# PCB_Albert.net
KiCad netlist of a schematic drawn in EAGLE
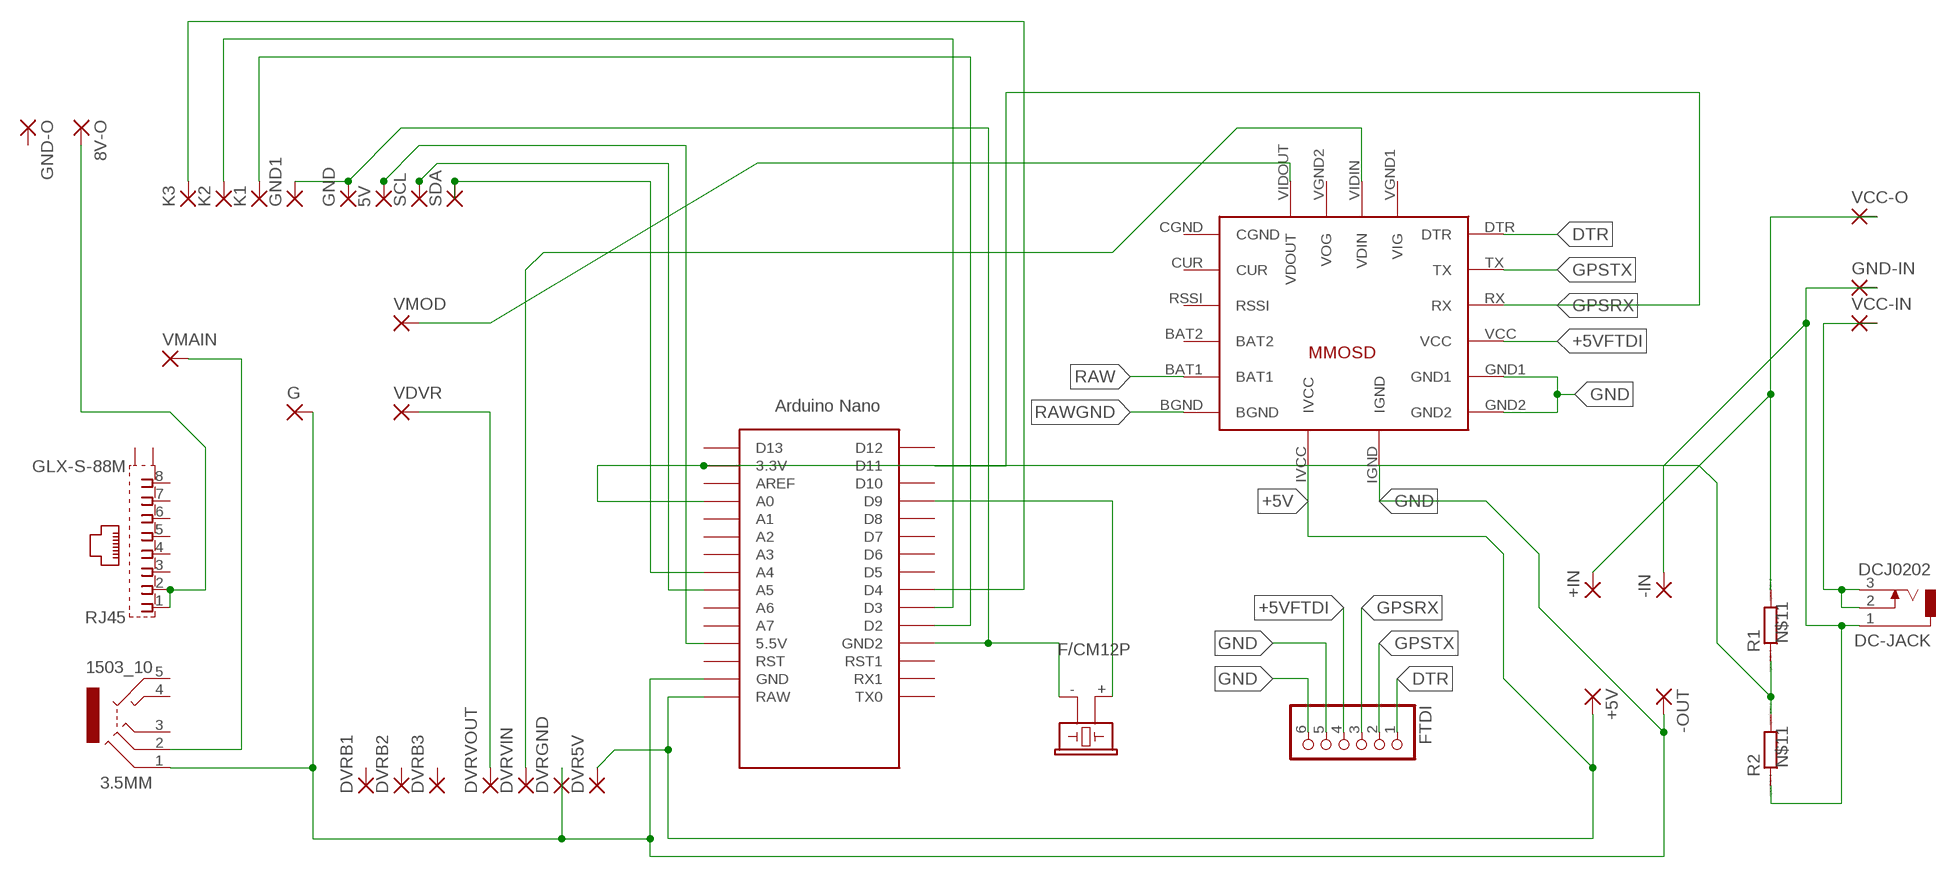
[diagram p0: schematic, sheet 1]

(export (version "E")
  (design (tool "Eeschema 10.0.6"))
  (components
    (comp (ref "+5V")
      (value "SMD2")
      (footprint "eagle-import:SMD1,27-2,54")
      (libsource (lib "eagle-import") (part "SMD2"))
    )
    (comp (ref "+IN")
      (value "SMD2")
      (footprint "eagle-import:SMD1,27-2,54")
      (libsource (lib "eagle-import") (part "SMD2"))
    )
    (comp (ref "-IN")
      (value "SMD2")
      (footprint "eagle-import:SMD1,27-2,54")
      (libsource (lib "eagle-import") (part "SMD2"))
    )
    (comp (ref "-OUT")
      (value "SMD2")
      (footprint "eagle-import:SMD1,27-2,54")
      (libsource (lib "eagle-import") (part "SMD2"))
    )
    (comp (ref "3.5MM")
      (value "1503_10")
      (footprint "eagle-import:1503_10")
      (libsource (lib "eagle-import") (part "1503_10"))
    )
    (comp (ref "5V")
      (value "SMD2")
      (footprint "eagle-import:SMD1,27-2,54")
      (libsource (lib "eagle-import") (part "SMD2"))
    )
    (comp (ref "8V-O")
      (value "2,54/1,1")
      (footprint "eagle-import:2,54_1,1")
      (libsource (lib "eagle-import") (part "2,54/1,1"))
    )
    (comp (ref "ADRUINO-NANO")
      (value "NANO")
      (footprint "eagle-import:NANO")
      (libsource (lib "eagle-import") (part "NANO"))
    )
    (comp (ref "BUZZ")
      (value "F/CM12P")
      (footprint "eagle-import:F_CM12P")
      (fields (field (name "SPICEPREFIX") "X"))
      (libsource (lib "eagle-import") (part "F/CM12P"))
    )
    (comp (ref "DC-JACK")
      (value "DCJ0202")
      (footprint "eagle-import:DCJ0202")
      (libsource (lib "eagle-import") (part "DCJ0202"))
    )
    (comp (ref "DVR5V")
      (value "SMD2")
      (footprint "eagle-import:SMD1,27-2,54")
      (libsource (lib "eagle-import") (part "SMD2"))
    )
    (comp (ref "DVRB1")
      (value "SMD2")
      (footprint "eagle-import:SMD1,27-2,54")
      (libsource (lib "eagle-import") (part "SMD2"))
    )
    (comp (ref "DVRB2")
      (value "SMD2")
      (footprint "eagle-import:SMD1,27-2,54")
      (libsource (lib "eagle-import") (part "SMD2"))
    )
    (comp (ref "DVRB3")
      (value "SMD2")
      (footprint "eagle-import:SMD1,27-2,54")
      (libsource (lib "eagle-import") (part "SMD2"))
    )
    (comp (ref "DVRGND")
      (value "SMD2")
      (footprint "eagle-import:SMD1,27-2,54")
      (libsource (lib "eagle-import") (part "SMD2"))
    )
    (comp (ref "DVRVIN")
      (value "SMD2")
      (footprint "eagle-import:SMD1,27-2,54")
      (libsource (lib "eagle-import") (part "SMD2"))
    )
    (comp (ref "DVRVOUT")
      (value "SMD2")
      (footprint "eagle-import:SMD1,27-2,54")
      (libsource (lib "eagle-import") (part "SMD2"))
    )
    (comp (ref "FTDI")
      (value "PINHD-1X6")
      (footprint "eagle-import:1X06")
      (libsource (lib "eagle-import") (part "PINHD-1X6"))
    )
    (comp (ref "G")
      (value "SMD2")
      (footprint "eagle-import:SMD1,27-2,54")
      (libsource (lib "eagle-import") (part "SMD2"))
    )
    (comp (ref "GND")
      (value "SMD2")
      (footprint "eagle-import:SMD1,27-2,54")
      (libsource (lib "eagle-import") (part "SMD2"))
    )
    (comp (ref "GND-IN")
      (value "2,54/1,1")
      (footprint "eagle-import:2,54_1,1")
      (libsource (lib "eagle-import") (part "2,54/1,1"))
    )
    (comp (ref "GND-O")
      (value "2,54/1,1")
      (footprint "eagle-import:2,54_1,1")
      (libsource (lib "eagle-import") (part "2,54/1,1"))
    )
    (comp (ref "GND1")
      (value "SMD2")
      (footprint "eagle-import:SMD1,27-2,54")
      (libsource (lib "eagle-import") (part "SMD2"))
    )
    (comp (ref "K1")
      (value "SMD2")
      (footprint "eagle-import:SMD1,27-2,54")
      (libsource (lib "eagle-import") (part "SMD2"))
    )
    (comp (ref "K2")
      (value "SMD2")
      (footprint "eagle-import:SMD1,27-2,54")
      (libsource (lib "eagle-import") (part "SMD2"))
    )
    (comp (ref "K3")
      (value "SMD2")
      (footprint "eagle-import:SMD1,27-2,54")
      (libsource (lib "eagle-import") (part "SMD2"))
    )
    (comp (ref "MINIMOSD")
      (value "MICROMINIMOSDPWR")
      (footprint "eagle-import:MMOSDNVDVID")
      (libsource (lib "eagle-import") (part "MICROMINIMOSDPWR"))
    )
    (comp (ref "R1")
      (value "R0207/10")
      (footprint "eagle-import:0207_10")
      (libsource (lib "eagle-import") (part "R0207/10"))
    )
    (comp (ref "R2")
      (value "R0207/10")
      (footprint "eagle-import:0207_10")
      (libsource (lib "eagle-import") (part "R0207/10"))
    )
    (comp (ref "RJ45")
      (value "GLX-S-88M")
      (footprint "eagle-import:GLX-S-88M")
      (libsource (lib "eagle-import") (part "GLX-S-88M"))
    )
    (comp (ref "SCL")
      (value "SMD2")
      (footprint "eagle-import:SMD1,27-2,54")
      (libsource (lib "eagle-import") (part "SMD2"))
    )
    (comp (ref "SDA")
      (value "SMD2")
      (footprint "eagle-import:SMD1,27-2,54")
      (libsource (lib "eagle-import") (part "SMD2"))
    )
    (comp (ref "VCC-IN")
      (value "2,54/1,1")
      (footprint "eagle-import:2,54_1,1")
      (libsource (lib "eagle-import") (part "2,54/1,1"))
    )
    (comp (ref "VCC-O")
      (value "2,54/1,1")
      (footprint "eagle-import:2,54_1,1")
      (libsource (lib "eagle-import") (part "2,54/1,1"))
    )
    (comp (ref "VDVR")
      (value "SMD2")
      (footprint "eagle-import:SMD1,27-2,54")
      (libsource (lib "eagle-import") (part "SMD2"))
    )
    (comp (ref "VMAIN")
      (value "SMD2")
      (footprint "eagle-import:SMD1,27-2,54")
      (libsource (lib "eagle-import") (part "SMD2"))
    )
    (comp (ref "VMOD")
      (value "SMD2")
      (footprint "eagle-import:SMD1,27-2,54")
      (libsource (lib "eagle-import") (part "SMD2"))
    )
  )
  (nets
    (net (code "1") (name "+5V") (class "Default")
      (node (ref "+5V") (pin "1") (pinfunction "P_1") (pintype "passive"))
      (node (ref "ADRUINO-NANO") (pin "RAW") (pinfunction "RAW_RAW") (pintype "bidirectional"))
      (node (ref "DVR5V") (pin "1") (pinfunction "P_1") (pintype "passive"))
      (node (ref "MINIMOSD") (pin "IVCC") (pinfunction "IVCC_IVCC") (pintype "power_in"))
    )
    (net (code "2") (name "+5VFTDI") (class "Default")
      (node (ref "FTDI") (pin "4") (pinfunction "4_4") (pintype "passive"))
      (node (ref "MINIMOSD") (pin "VCC") (pinfunction "VCC_VCC") (pintype "power_in"))
    )
    (net (code "3") (name "/BAT2") (class "Default")
      (node (ref "MINIMOSD") (pin "BAT2") (pinfunction "BAT2_BAT2") (pintype "power_in"))
    )
    (net (code "4") (name "/CGND") (class "Default")
      (node (ref "MINIMOSD") (pin "CGND") (pinfunction "CGND_CGND") (pintype "power_in"))
    )
    (net (code "5") (name "/N$11") (class "Default")
      (node (ref "-IN") (pin "1") (pinfunction "P_1") (pintype "passive"))
      (node (ref "DC-JACK") (pin "1") (pinfunction "1_1") (pintype "passive"))
      (node (ref "GND-IN") (pin "1") (pinfunction "P_1") (pintype "passive"))
      (node (ref "R2") (pin "1") (pinfunction "1_1") (pintype "passive"))
    )
    (net (code "6") (name "DTR") (class "Default")
      (node (ref "FTDI") (pin "1") (pinfunction "1_1") (pintype "passive"))
      (node (ref "MINIMOSD") (pin "DTR") (pinfunction "DTR_DTR") (pintype "bidirectional"))
    )
    (net (code "7") (name "GND") (class "Default")
      (node (ref "-OUT") (pin "1") (pinfunction "P_1") (pintype "passive"))
      (node (ref "3.5MM") (pin "1") (pinfunction "1_1") (pintype "passive"))
      (node (ref "ADRUINO-NANO") (pin "GND") (pinfunction "GND_GND") (pintype "bidirectional"))
      (node (ref "DVRGND") (pin "1") (pinfunction "P_1") (pintype "passive"))
      (node (ref "FTDI") (pin "5") (pinfunction "5_5") (pintype "passive"))
      (node (ref "FTDI") (pin "6") (pinfunction "6_6") (pintype "passive"))
      (node (ref "G") (pin "1") (pinfunction "P_1") (pintype "passive"))
      (node (ref "MINIMOSD") (pin "GND1") (pinfunction "GND1_GND1") (pintype "power_in"))
      (node (ref "MINIMOSD") (pin "GND2") (pinfunction "GND2_GND2") (pintype "power_in"))
      (node (ref "MINIMOSD") (pin "IGND") (pinfunction "IGND_IGND") (pintype "power_in"))
    )
    (net (code "8") (name "GPSRX") (class "Default")
      (node (ref "ADRUINO-NANO") (pin "D11") (pinfunction "D11_D11") (pintype "bidirectional"))
      (node (ref "FTDI") (pin "3") (pinfunction "3_3") (pintype "passive"))
      (node (ref "MINIMOSD") (pin "RX") (pinfunction "RX_RX") (pintype "input"))
    )
    (net (code "9") (name "GPSTX") (class "Default")
      (node (ref "FTDI") (pin "2") (pinfunction "2_2") (pintype "passive"))
      (node (ref "MINIMOSD") (pin "TX") (pinfunction "TX_TX") (pintype "output"))
    )
    (net (code "10") (name "Net-(+IN-P)") (class "Default")
      (node (ref "+IN") (pin "1") (pinfunction "P_1") (pintype "passive"))
      (node (ref "R1") (pin "2") (pinfunction "2_2") (pintype "passive"))
      (node (ref "VCC-O") (pin "1") (pinfunction "P_1") (pintype "passive"))
    )
    (net (code "11") (name "Net-(5V-P)") (class "Default")
      (node (ref "5V") (pin "1") (pinfunction "P_1") (pintype "passive"))
      (node (ref "ADRUINO-NANO") (pin "5V") (pinfunction "5.5V_5V") (pintype "bidirectional"))
    )
    (net (code "12") (name "Net-(8V-O-P)") (class "Default")
      (node (ref "8V-O") (pin "1") (pinfunction "P_1") (pintype "passive"))
      (node (ref "RJ45") (pin "1") (pinfunction "1_1") (pintype "passive"))
      (node (ref "RJ45") (pin "2") (pinfunction "2_2") (pintype "passive"))
    )
    (net (code "13") (name "Net-(ADRUINO-NANO-GND2)") (class "Default")
      (node (ref "ADRUINO-NANO") (pin "GND1") (pinfunction "GND2_GND1") (pintype "bidirectional"))
      (node (ref "BUZZ") (pin "-") (pinfunction "2_-") (pintype "passive"))
      (node (ref "GND") (pin "1") (pinfunction "P_1") (pintype "passive"))
      (node (ref "GND1") (pin "1") (pinfunction "P_1") (pintype "passive"))
    )
    (net (code "14") (name "Net-(ADRUINO-NANO-Pad3.3V)") (class "Default")
      (node (ref "ADRUINO-NANO") (pin "3.3V") (pinfunction "3.3V_3.3V") (pintype "bidirectional"))
      (node (ref "ADRUINO-NANO") (pin "A0") (pinfunction "A0_A0") (pintype "bidirectional"))
      (node (ref "R1") (pin "1") (pinfunction "1_1") (pintype "passive"))
      (node (ref "R2") (pin "2") (pinfunction "2_2") (pintype "passive"))
    )
    (net (code "15") (name "Net-(BUZZ-1)") (class "Default")
      (node (ref "ADRUINO-NANO") (pin "D9") (pinfunction "D9_D9") (pintype "bidirectional"))
      (node (ref "BUZZ") (pin "+") (pinfunction "1_+") (pintype "passive"))
    )
    (net (code "16") (name "Net-(DVRVIN-P)") (class "Default")
      (node (ref "DVRVIN") (pin "1") (pinfunction "P_1") (pintype "passive"))
      (node (ref "MINIMOSD") (pin "VIDIN") (pinfunction "VDIN_VIDIN") (pintype "input"))
    )
    (net (code "17") (name "Net-(DVRVOUT-P)") (class "Default")
      (node (ref "DVRVOUT") (pin "1") (pinfunction "P_1") (pintype "passive"))
      (node (ref "VDVR") (pin "1") (pinfunction "P_1") (pintype "passive"))
    )
    (net (code "18") (name "Net-(K1-P)") (class "Default")
      (node (ref "ADRUINO-NANO") (pin "D2") (pinfunction "D2_D2") (pintype "bidirectional"))
      (node (ref "K1") (pin "1") (pinfunction "P_1") (pintype "passive"))
    )
    (net (code "19") (name "Net-(K2-P)") (class "Default")
      (node (ref "ADRUINO-NANO") (pin "D3") (pinfunction "D3_D3") (pintype "bidirectional"))
      (node (ref "K2") (pin "1") (pinfunction "P_1") (pintype "passive"))
    )
    (net (code "20") (name "Net-(K3-P)") (class "Default")
      (node (ref "ADRUINO-NANO") (pin "D4") (pinfunction "D4_D4") (pintype "bidirectional"))
      (node (ref "K3") (pin "1") (pinfunction "P_1") (pintype "passive"))
    )
    (net (code "21") (name "Net-(MINIMOSD-VDOUT)") (class "Default")
      (node (ref "MINIMOSD") (pin "VIDOUT") (pinfunction "VDOUT_VIDOUT") (pintype "output"))
      (node (ref "VMOD") (pin "1") (pinfunction "P_1") (pintype "passive"))
    )
    (net (code "22") (name "Net-(SCL-P)") (class "Default")
      (node (ref "ADRUINO-NANO") (pin "A5") (pinfunction "A5_A5") (pintype "bidirectional"))
      (node (ref "SCL") (pin "1") (pinfunction "P_1") (pintype "passive"))
    )
    (net (code "23") (name "Net-(SDA-P)") (class "Default")
      (node (ref "ADRUINO-NANO") (pin "A4") (pinfunction "A4_A4") (pintype "bidirectional"))
      (node (ref "SDA") (pin "1") (pinfunction "P_1") (pintype "passive"))
    )
    (net (code "24") (name "Net-(VCC-IN-P)") (class "Default")
      (node (ref "DC-JACK") (pin "2") (pinfunction "2_2") (pintype "passive"))
      (node (ref "DC-JACK") (pin "3") (pinfunction "3_3") (pintype "passive"))
      (node (ref "VCC-IN") (pin "1") (pinfunction "P_1") (pintype "passive"))
    )
    (net (code "25") (name "Net-(VMAIN-P)") (class "Default")
      (node (ref "3.5MM") (pin "2") (pinfunction "2_2") (pintype "passive"))
      (node (ref "VMAIN") (pin "1") (pinfunction "P_1") (pintype "passive"))
    )
    (net (code "26") (name "RAW") (class "Default")
      (node (ref "MINIMOSD") (pin "BAT1") (pinfunction "BAT1_BAT1") (pintype "power_in"))
    )
    (net (code "27") (name "RAWGND") (class "Default")
      (node (ref "MINIMOSD") (pin "BGND") (pinfunction "BGND_BGND") (pintype "power_in"))
    )
    (net (code "28") (name "unconnected-(3.5MM-Pad3)") (class "Default")
      (node (ref "3.5MM") (pin "3") (pinfunction "3_3") (pintype "passive"))
    )
    (net (code "29") (name "unconnected-(3.5MM-Pad4)") (class "Default")
      (node (ref "3.5MM") (pin "4") (pinfunction "4_4") (pintype "passive"))
    )
    (net (code "30") (name "unconnected-(3.5MM-Pad5)") (class "Default")
      (node (ref "3.5MM") (pin "5") (pinfunction "5_5") (pintype "passive"))
    )
    (net (code "31") (name "unconnected-(ADRUINO-NANO-PadA1)") (class "Default")
      (node (ref "ADRUINO-NANO") (pin "A1") (pinfunction "A1_A1") (pintype "bidirectional"))
    )
    (net (code "32") (name "unconnected-(ADRUINO-NANO-PadA2)") (class "Default")
      (node (ref "ADRUINO-NANO") (pin "A2") (pinfunction "A2_A2") (pintype "bidirectional"))
    )
    (net (code "33") (name "unconnected-(ADRUINO-NANO-PadA3)") (class "Default")
      (node (ref "ADRUINO-NANO") (pin "A3") (pinfunction "A3_A3") (pintype "bidirectional"))
    )
    (net (code "34") (name "unconnected-(ADRUINO-NANO-PadA6)") (class "Default")
      (node (ref "ADRUINO-NANO") (pin "A6") (pinfunction "A6_A6") (pintype "bidirectional"))
    )
    (net (code "35") (name "unconnected-(ADRUINO-NANO-PadA7)") (class "Default")
      (node (ref "ADRUINO-NANO") (pin "A7") (pinfunction "A7_A7") (pintype "bidirectional"))
    )
    (net (code "36") (name "unconnected-(ADRUINO-NANO-PadAREF)") (class "Default")
      (node (ref "ADRUINO-NANO") (pin "AREF") (pinfunction "AREF_AREF") (pintype "bidirectional"))
    )
    (net (code "37") (name "unconnected-(ADRUINO-NANO-PadD5)") (class "Default")
      (node (ref "ADRUINO-NANO") (pin "D5") (pinfunction "D5_D5") (pintype "bidirectional"))
    )
    (net (code "38") (name "unconnected-(ADRUINO-NANO-PadD6)") (class "Default")
      (node (ref "ADRUINO-NANO") (pin "D6") (pinfunction "D6_D6") (pintype "bidirectional"))
    )
    (net (code "39") (name "unconnected-(ADRUINO-NANO-PadD7)") (class "Default")
      (node (ref "ADRUINO-NANO") (pin "D7") (pinfunction "D7_D7") (pintype "bidirectional"))
    )
    (net (code "40") (name "unconnected-(ADRUINO-NANO-PadD8)") (class "Default")
      (node (ref "ADRUINO-NANO") (pin "D8") (pinfunction "D8_D8") (pintype "bidirectional"))
    )
    (net (code "41") (name "unconnected-(ADRUINO-NANO-PadD10)") (class "Default")
      (node (ref "ADRUINO-NANO") (pin "D10") (pinfunction "D10_D10") (pintype "bidirectional"))
    )
    (net (code "42") (name "unconnected-(ADRUINO-NANO-PadD12)") (class "Default")
      (node (ref "ADRUINO-NANO") (pin "D12") (pinfunction "D12_D12") (pintype "bidirectional"))
    )
    (net (code "43") (name "unconnected-(ADRUINO-NANO-PadD13)") (class "Default")
      (node (ref "ADRUINO-NANO") (pin "D13") (pinfunction "D13_D13") (pintype "bidirectional"))
    )
    (net (code "44") (name "unconnected-(ADRUINO-NANO-PadICSP1)") (class "Default")
      (node (ref "ADRUINO-NANO") (pin "ICSP1") (pinfunction "ICSP1_ICSP1") (pintype "bidirectional"))
    )
    (net (code "45") (name "unconnected-(ADRUINO-NANO-PadICSP2)") (class "Default")
      (node (ref "ADRUINO-NANO") (pin "ICSP2") (pinfunction "ICSP2_ICSP2") (pintype "bidirectional"))
    )
    (net (code "46") (name "unconnected-(ADRUINO-NANO-PadICSP3)") (class "Default")
      (node (ref "ADRUINO-NANO") (pin "ICSP3") (pinfunction "ICSP3_ICSP3") (pintype "bidirectional"))
    )
    (net (code "47") (name "unconnected-(ADRUINO-NANO-PadICSP4)") (class "Default")
      (node (ref "ADRUINO-NANO") (pin "ICSP4") (pinfunction "ICSP4_ICSP4") (pintype "bidirectional"))
    )
    (net (code "48") (name "unconnected-(ADRUINO-NANO-PadICSP5)") (class "Default")
      (node (ref "ADRUINO-NANO") (pin "ICSP5") (pinfunction "ICSP5_ICSP5") (pintype "bidirectional"))
    )
    (net (code "49") (name "unconnected-(ADRUINO-NANO-PadICSP6)") (class "Default")
      (node (ref "ADRUINO-NANO") (pin "ICSP6") (pinfunction "ICSP6_ICSP6") (pintype "bidirectional"))
    )
    (net (code "50") (name "unconnected-(ADRUINO-NANO-PadRST)") (class "Default")
      (node (ref "ADRUINO-NANO") (pin "RST") (pinfunction "RST_RST") (pintype "bidirectional"))
    )
    (net (code "51") (name "unconnected-(ADRUINO-NANO-PadRST1)") (class "Default")
      (node (ref "ADRUINO-NANO") (pin "RST1") (pinfunction "RST1_RST1") (pintype "bidirectional"))
    )
    (net (code "52") (name "unconnected-(ADRUINO-NANO-PadRX1)") (class "Default")
      (node (ref "ADRUINO-NANO") (pin "RX1") (pinfunction "RX1_RX1") (pintype "bidirectional"))
    )
    (net (code "53") (name "unconnected-(ADRUINO-NANO-PadTX0)") (class "Default")
      (node (ref "ADRUINO-NANO") (pin "TX0") (pinfunction "TX0_TX0") (pintype "bidirectional"))
    )
    (net (code "54") (name "unconnected-(DVRB1-P-Pad1)") (class "Default")
      (node (ref "DVRB1") (pin "1") (pinfunction "P_1") (pintype "passive"))
    )
    (net (code "55") (name "unconnected-(DVRB2-P-Pad1)") (class "Default")
      (node (ref "DVRB2") (pin "1") (pinfunction "P_1") (pintype "passive"))
    )
    (net (code "56") (name "unconnected-(DVRB3-P-Pad1)") (class "Default")
      (node (ref "DVRB3") (pin "1") (pinfunction "P_1") (pintype "passive"))
    )
    (net (code "57") (name "unconnected-(GND-O-P-Pad1)") (class "Default")
      (node (ref "GND-O") (pin "1") (pinfunction "P_1") (pintype "passive"))
    )
    (net (code "58") (name "unconnected-(MINIMOSD-PadCUR)") (class "Default")
      (node (ref "MINIMOSD") (pin "CUR") (pinfunction "CUR_CUR") (pintype "bidirectional"))
    )
    (net (code "59") (name "unconnected-(MINIMOSD-PadRSSI)") (class "Default")
      (node (ref "MINIMOSD") (pin "RSSI") (pinfunction "RSSI_RSSI") (pintype "bidirectional"))
    )
    (net (code "60") (name "unconnected-(MINIMOSD-VIG-PadVGND1)") (class "Default")
      (node (ref "MINIMOSD") (pin "VGND1") (pinfunction "VIG_VGND1") (pintype "input"))
    )
    (net (code "61") (name "unconnected-(MINIMOSD-VOG-PadVGND2)") (class "Default")
      (node (ref "MINIMOSD") (pin "VGND2") (pinfunction "VOG_VGND2") (pintype "output"))
    )
    (net (code "62") (name "unconnected-(RJ45-Pad3)") (class "Default")
      (node (ref "RJ45") (pin "3") (pinfunction "3_3") (pintype "passive"))
    )
    (net (code "63") (name "unconnected-(RJ45-Pad4)") (class "Default")
      (node (ref "RJ45") (pin "4") (pinfunction "4_4") (pintype "passive"))
    )
    (net (code "64") (name "unconnected-(RJ45-Pad5)") (class "Default")
      (node (ref "RJ45") (pin "5") (pinfunction "5_5") (pintype "passive"))
    )
    (net (code "65") (name "unconnected-(RJ45-Pad6)") (class "Default")
      (node (ref "RJ45") (pin "6") (pinfunction "6_6") (pintype "passive"))
    )
    (net (code "66") (name "unconnected-(RJ45-Pad7)") (class "Default")
      (node (ref "RJ45") (pin "7") (pinfunction "7_7") (pintype "passive"))
    )
    (net (code "67") (name "unconnected-(RJ45-Pad8)") (class "Default")
      (node (ref "RJ45") (pin "8") (pinfunction "8_8") (pintype "passive"))
    )
    (net (code "68") (name "unconnected-(RJ45-PadS1)") (class "Default")
      (node (ref "RJ45") (pin "S1") (pinfunction "S1_S1") (pintype "passive"))
    )
    (net (code "69") (name "unconnected-(RJ45-PadS2)") (class "Default")
      (node (ref "RJ45") (pin "S2") (pinfunction "S2_S2") (pintype "passive"))
    )
  )
)
